# LEDBAKL_TPS61040DBV.net
KiCad netlist of a schematic drawn in Altium Designer
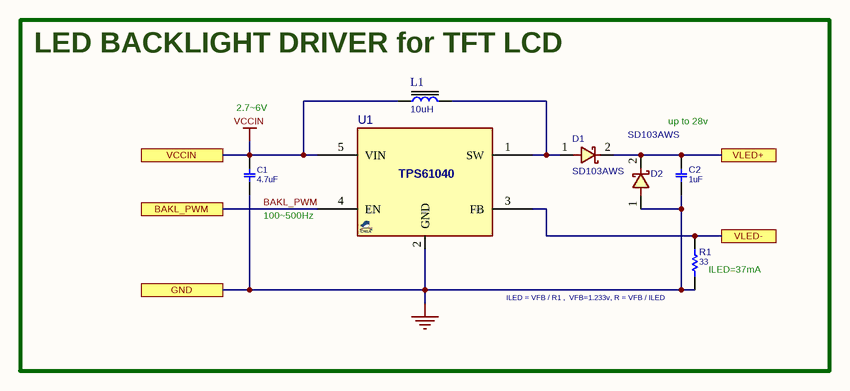
[diagram p0: LEDBAKL_TPS61040DBV.SchDoc]

(export (version "E")
  (design (tool "Eeschema 10.0.6"))
  (components
    (comp (ref "C1")
      (value "4.7uF")
      (footprint "C0402")
      (description "CAP, MLCC")
      (fields (field (name "MANF_P#") "CL05A475MP5NRNC") (field (name "MANF") "Samsung"))
      (libsource (lib "passive_smd") (part "CAP_SMD_MLCC"))
    )
    (comp (ref "C2")
      (value "1uF")
      (footprint "C0603")
      (description "CAP, MLCC")
      (fields (field (name "MANF_P#") "CL10A105KB8NNNC") (field (name "MANF") "Samsung"))
      (libsource (lib "passive_smd") (part "CAP_SMD_MLCC"))
    )
    (comp (ref "D1")
      (value "SD103AWS")
      (footprint "D_SOD323")
      (description "DIODE, SCHOTTKY, 40V, 2A")
      (fields (field (name "MANF") "DIODES"))
      (libsource (lib "diode") (part "DIODE_SMD_SCHOTTKY_1N5819"))
    )
    (comp (ref "D2")
      (value "SD103AWS")
      (footprint "D_SOD323")
      (description "DIODE, SCHOTTKY, 40V, 2A")
      (fields (field (name "MANF") "DIODES"))
      (libsource (lib "diode") (part "DIODE_SMD_SCHOTTKY_1N5819"))
    )
    (comp (ref "L1")
      (value "10uH")
      (footprint "L_4")
      (description "INDUCTOR, POWER, SMD")
      (fields (field (name "MANF_P#") "GCD43-100MC"))
      (libsource (lib "passive") (part "INDPWR_SMD"))
    )
    (comp (ref "R1")
      (value "33")
      (footprint "R0402")
      (description "RESISTOR, SMD, 20K, 0402")
      (fields (field (name "MANF") "Yageo") (field (name "MANF_P#") "RK73H1ETTP2002F"))
      (libsource (lib "chila_passive") (part "RES_SMD"))
    )
    (comp (ref "U1")
      (value "TPS61040")
      (footprint "SOT23_5")
      (description "REG, Switching, Boost, 0.4A, ADJ, 1MHz, SOT-23-5")
      (fields (field (name "MANF_P#") "TPS61040DBVR") (field (name "MANF") "TI"))
      (libsource (lib "pwr_switching_boost") (part "VREG_TPS61040_SOT23"))
    )
  )
  (nets
    (net (code "1") (name "/BAKL_PWM") (class "Default")
      (node (ref "U1") (pin "4") (pinfunction "EN_4") (pintype "tri_state"))
    )
    (net (code "2") (name "/VLED+") (class "Default")
      (node (ref "C2") (pin "2") (pinfunction "2_2") (pintype "passive"))
      (node (ref "D1") (pin "2") (pinfunction "2_2") (pintype "passive"))
      (node (ref "D2") (pin "2") (pinfunction "2_2") (pintype "passive"))
    )
    (net (code "3") (name "/VLED-") (class "Default")
      (node (ref "R1") (pin "1") (pinfunction "1_1") (pintype "passive"))
      (node (ref "U1") (pin "3") (pinfunction "FB_3") (pintype "tri_state"))
    )
    (net (code "4") (name "GND") (class "Default")
      (node (ref "C1") (pin "1") (pinfunction "1_1") (pintype "passive"))
      (node (ref "C2") (pin "1") (pinfunction "1_1") (pintype "passive"))
      (node (ref "D2") (pin "1") (pinfunction "1_1") (pintype "passive"))
      (node (ref "R1") (pin "2") (pinfunction "2_2") (pintype "passive"))
      (node (ref "U1") (pin "2") (pinfunction "GND_2") (pintype "tri_state"))
    )
    (net (code "5") (name "Net-(U1-SW)") (class "Default")
      (node (ref "D1") (pin "1") (pinfunction "1_1") (pintype "passive"))
      (node (ref "L1") (pin "2") (pinfunction "2_2") (pintype "passive"))
      (node (ref "U1") (pin "1") (pinfunction "SW_1") (pintype "tri_state"))
    )
    (net (code "6") (name "VCCIN") (class "Default")
      (node (ref "C1") (pin "2") (pinfunction "2_2") (pintype "passive"))
      (node (ref "L1") (pin "1") (pinfunction "1_1") (pintype "passive"))
      (node (ref "U1") (pin "5") (pinfunction "VIN_5") (pintype "tri_state"))
    )
  )
)
